# Lab_3.net
KiCad netlist of a schematic drawn in EAGLE
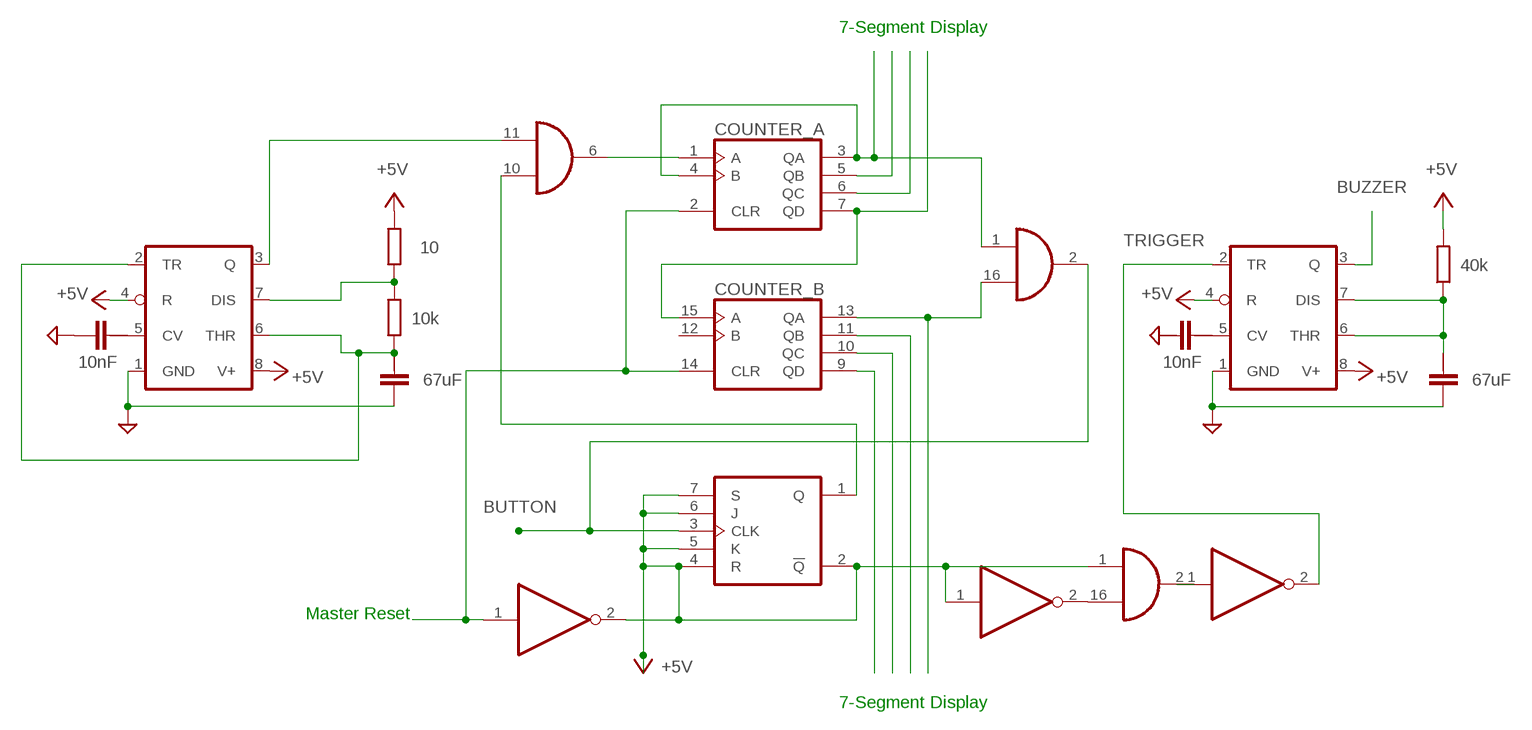
[diagram p0: schematic, sheet 1]

(export (version "E")
  (design (tool "Eeschema 10.0.6"))
  (components
    (comp (ref "AND_GATE_")
      (value "74AC11008")
      (footprint "eagle-import:DIL16")
      (libsource (lib "eagle-import") (part "74AC11008"))
    )
    (comp (ref "AND_GATE_1")
      (value "74AC11008")
      (footprint "eagle-import:DIL16")
      (libsource (lib "eagle-import") (part "74AC11008"))
    )
    (comp (ref "C1")
      (value "10nF")
      (footprint "eagle-import:C2.5_5-4")
      (libsource (lib "eagle-import") (part "C-2.5-5/4"))
    )
    (comp (ref "C2")
      (value "67uF")
      (footprint "eagle-import:C2.5_5-4")
      (libsource (lib "eagle-import") (part "C-2.5-5/4"))
    )
    (comp (ref "C3")
      (value "67uF")
      (footprint "eagle-import:C2.5_5-4")
      (libsource (lib "eagle-import") (part "C-2.5-5/4"))
    )
    (comp (ref "C4")
      (value "10nF")
      (footprint "eagle-import:C2.5_5-4")
      (libsource (lib "eagle-import") (part "C-2.5-5/4"))
    )
    (comp (ref "COUNTER_")
      (value "74AC390N")
      (footprint "eagle-import:DIL16")
      (libsource (lib "eagle-import") (part "74390NAC"))
    )
    (comp (ref "IC1")
      (value "LM555D")
      (footprint "eagle-import:SO08")
      (libsource (lib "eagle-import") (part "555DLM"))
    )
    (comp (ref "IC2")
      (value "LM555D")
      (footprint "eagle-import:SO08")
      (libsource (lib "eagle-import") (part "555DLM"))
    )
    (comp (ref "JK_FLIP-FLOP_")
      (value "4027N")
      (footprint "eagle-import:DIL16")
      (libsource (lib "eagle-import") (part "4027N"))
    )
    (comp (ref "NOT_GATE_")
      (value "74ALS04N")
      (footprint "eagle-import:DIL14")
      (libsource (lib "eagle-import") (part "7404NALS"))
    )
    (comp (ref "NOT_GATE_1")
      (value "74ALS04N")
      (footprint "eagle-import:DIL14")
      (libsource (lib "eagle-import") (part "7404NALS"))
    )
    (comp (ref "NOT_GATE_2")
      (value "74ALS04N")
      (footprint "eagle-import:DIL14")
      (libsource (lib "eagle-import") (part "7404NALS"))
    )
    (comp (ref "R1")
      (value "40k")
      (footprint "eagle-import:0204_7")
      (libsource (lib "eagle-import") (part "R-EU_0204/7"))
    )
    (comp (ref "R2")
      (value "10")
      (footprint "eagle-import:0204_7")
      (libsource (lib "eagle-import") (part "R-EU_0204/7"))
    )
    (comp (ref "R3")
      (value "10k")
      (footprint "eagle-import:0204_7")
      (libsource (lib "eagle-import") (part "R-EU_0204/7"))
    )
  )
  (nets
    (net (code "1") (name "+5V") (class "Default")
      (node (ref "AND_GATE_1") (pin "1") (pinfunction "I0_1") (pintype "input"))
      (node (ref "IC1") (pin "4") (pinfunction "R_4") (pintype "input"))
      (node (ref "IC1") (pin "8") (pinfunction "V+_8") (pintype "power_in"))
      (node (ref "IC2") (pin "4") (pinfunction "R_4") (pintype "input"))
      (node (ref "IC2") (pin "8") (pinfunction "V+_8") (pintype "power_in"))
      (node (ref "JK_FLIP-FLOP_") (pin "2") (pinfunction "~{Q}_2") (pintype "output"))
      (node (ref "JK_FLIP-FLOP_") (pin "4") (pinfunction "R_4") (pintype "input"))
      (node (ref "JK_FLIP-FLOP_") (pin "5") (pinfunction "K_5") (pintype "input"))
      (node (ref "JK_FLIP-FLOP_") (pin "6") (pinfunction "J_6") (pintype "input"))
      (node (ref "JK_FLIP-FLOP_") (pin "7") (pinfunction "S_7") (pintype "input"))
      (node (ref "NOT_GATE_") (pin "2") (pinfunction "O_2") (pintype "output"))
      (node (ref "NOT_GATE_1") (pin "1") (pinfunction "I_1") (pintype "input"))
      (node (ref "R1") (pin "2") (pinfunction "2_2") (pintype "passive"))
      (node (ref "R2") (pin "2") (pinfunction "2_2") (pintype "passive"))
    )
    (net (code "2") (name "/BUTTON") (class "Default")
      (node (ref "AND_GATE_") (pin "2") (pinfunction "O_2") (pintype "output"))
      (node (ref "JK_FLIP-FLOP_") (pin "3") (pinfunction "CLK_3") (pintype "input"))
    )
    (net (code "3") (name "/BUZZER") (class "Default")
      (node (ref "IC1") (pin "3") (pinfunction "Q_3") (pintype "output"))
    )
    (net (code "4") (name "/TRIGGER") (class "Default")
      (node (ref "IC1") (pin "2") (pinfunction "TR_2") (pintype "input"))
      (node (ref "NOT_GATE_2") (pin "2") (pinfunction "O_2") (pintype "output"))
    )
    (net (code "5") (name "GND") (class "Default")
      (node (ref "C2") (pin "1") (pinfunction "1_1") (pintype "passive"))
      (node (ref "C3") (pin "1") (pinfunction "1_1") (pintype "passive"))
      (node (ref "C4") (pin "1") (pinfunction "1_1") (pintype "passive"))
      (node (ref "IC1") (pin "1") (pinfunction "GND_1") (pintype "power_in"))
      (node (ref "IC2") (pin "1") (pinfunction "GND_1") (pintype "power_in"))
    )
    (net (code "6") (name "Net-(AND_GATE_1A-I1)") (class "Default")
      (node (ref "AND_GATE_1") (pin "16") (pinfunction "I1_16") (pintype "input"))
      (node (ref "NOT_GATE_1") (pin "2") (pinfunction "O_2") (pintype "output"))
    )
    (net (code "7") (name "Net-(AND_GATE_1A-O)") (class "Default")
      (node (ref "AND_GATE_1") (pin "2") (pinfunction "O_2") (pintype "output"))
      (node (ref "NOT_GATE_2") (pin "1") (pinfunction "I_1") (pintype "input"))
    )
    (net (code "8") (name "Net-(AND_GATE_A-I0)") (class "Default")
      (node (ref "AND_GATE_") (pin "1") (pinfunction "I0_1") (pintype "input"))
      (node (ref "COUNTER_") (pin "3") (pinfunction "QA_3") (pintype "output"))
      (node (ref "COUNTER_") (pin "4") (pinfunction "B_4") (pintype "input"))
    )
    (net (code "9") (name "Net-(AND_GATE_A-I1)") (class "Default")
      (node (ref "AND_GATE_") (pin "16") (pinfunction "I1_16") (pintype "input"))
      (node (ref "COUNTER_") (pin "13") (pinfunction "QA_13") (pintype "output"))
    )
    (net (code "10") (name "Net-(AND_GATE_C-I0)") (class "Default")
      (node (ref "AND_GATE_") (pin "11") (pinfunction "I0_11") (pintype "input"))
      (node (ref "IC2") (pin "3") (pinfunction "Q_3") (pintype "output"))
    )
    (net (code "11") (name "Net-(AND_GATE_C-I1)") (class "Default")
      (node (ref "AND_GATE_") (pin "10") (pinfunction "I1_10") (pintype "input"))
      (node (ref "JK_FLIP-FLOP_") (pin "1") (pinfunction "Q_1") (pintype "output"))
    )
    (net (code "12") (name "Net-(AND_GATE_C-O)") (class "Default")
      (node (ref "AND_GATE_") (pin "6") (pinfunction "O_6") (pintype "output"))
      (node (ref "COUNTER_") (pin "1") (pinfunction "A_1") (pintype "input"))
    )
    (net (code "13") (name "Net-(COUNTER_A-CLR)") (class "Default")
      (node (ref "COUNTER_") (pin "14") (pinfunction "CLR_14") (pintype "input"))
      (node (ref "COUNTER_") (pin "2") (pinfunction "CLR_2") (pintype "input"))
      (node (ref "NOT_GATE_") (pin "1") (pinfunction "I_1") (pintype "input"))
    )
    (net (code "14") (name "Net-(COUNTER_A-QD)") (class "Default")
      (node (ref "COUNTER_") (pin "15") (pinfunction "A_15") (pintype "input"))
      (node (ref "COUNTER_") (pin "7") (pinfunction "QD_7") (pintype "output"))
    )
    (net (code "15") (name "Net-(IC1-CV)") (class "Default")
      (node (ref "C1") (pin "2") (pinfunction "2_2") (pintype "passive"))
      (node (ref "IC1") (pin "5") (pinfunction "CV_5") (pintype "input"))
    )
    (net (code "16") (name "Net-(IC1-DIS)") (class "Default")
      (node (ref "C2") (pin "2") (pinfunction "2_2") (pintype "passive"))
      (node (ref "IC1") (pin "6") (pinfunction "THR_6") (pintype "input"))
      (node (ref "IC1") (pin "7") (pinfunction "DIS_7") (pintype "input"))
      (node (ref "R1") (pin "1") (pinfunction "1_1") (pintype "passive"))
    )
    (net (code "17") (name "Net-(IC2-CV)") (class "Default")
      (node (ref "C4") (pin "2") (pinfunction "2_2") (pintype "passive"))
      (node (ref "IC2") (pin "5") (pinfunction "CV_5") (pintype "input"))
    )
    (net (code "18") (name "Net-(IC2-DIS)") (class "Default")
      (node (ref "IC2") (pin "7") (pinfunction "DIS_7") (pintype "input"))
      (node (ref "R2") (pin "1") (pinfunction "1_1") (pintype "passive"))
      (node (ref "R3") (pin "2") (pinfunction "2_2") (pintype "passive"))
    )
    (net (code "19") (name "Net-(IC2-THR)") (class "Default")
      (node (ref "C3") (pin "2") (pinfunction "2_2") (pintype "passive"))
      (node (ref "IC2") (pin "2") (pinfunction "TR_2") (pintype "input"))
      (node (ref "IC2") (pin "6") (pinfunction "THR_6") (pintype "input"))
      (node (ref "R3") (pin "1") (pinfunction "1_1") (pintype "passive"))
    )
    (net (code "20") (name "unconnected-(C1-Pad1)") (class "Default")
      (node (ref "C1") (pin "1") (pinfunction "1_1") (pintype "passive"))
    )
    (net (code "21") (name "unconnected-(C1-Pad3)") (class "Default")
      (node (ref "C1") (pin "3") (pinfunction "3_3") (pintype "passive"))
    )
    (net (code "22") (name "unconnected-(C2-Pad3)") (class "Default")
      (node (ref "C2") (pin "3") (pinfunction "3_3") (pintype "passive"))
    )
    (net (code "23") (name "unconnected-(C3-Pad3)") (class "Default")
      (node (ref "C3") (pin "3") (pinfunction "3_3") (pintype "passive"))
    )
    (net (code "24") (name "unconnected-(C4-Pad3)") (class "Default")
      (node (ref "C4") (pin "3") (pinfunction "3_3") (pintype "passive"))
    )
    (net (code "25") (name "unconnected-(COUNTER_A-QB-Pad5)") (class "Default")
      (node (ref "COUNTER_") (pin "5") (pinfunction "QB_5") (pintype "output"))
    )
    (net (code "26") (name "unconnected-(COUNTER_A-QC-Pad6)") (class "Default")
      (node (ref "COUNTER_") (pin "6") (pinfunction "QC_6") (pintype "output"))
    )
    (net (code "27") (name "unconnected-(COUNTER_B-B-Pad12)") (class "Default")
      (node (ref "COUNTER_") (pin "12") (pinfunction "B_12") (pintype "input"))
    )
    (net (code "28") (name "unconnected-(COUNTER_B-QB-Pad11)") (class "Default")
      (node (ref "COUNTER_") (pin "11") (pinfunction "QB_11") (pintype "output"))
    )
    (net (code "29") (name "unconnected-(COUNTER_B-QC-Pad10)") (class "Default")
      (node (ref "COUNTER_") (pin "10") (pinfunction "QC_10") (pintype "output"))
    )
    (net (code "30") (name "unconnected-(COUNTER_B-QD-Pad9)") (class "Default")
      (node (ref "COUNTER_") (pin "9") (pinfunction "QD_9") (pintype "output"))
    )
  )
)
